# 06_-_PERIPHERAL.net
KiCad netlist of a schematic drawn in Altium Designer
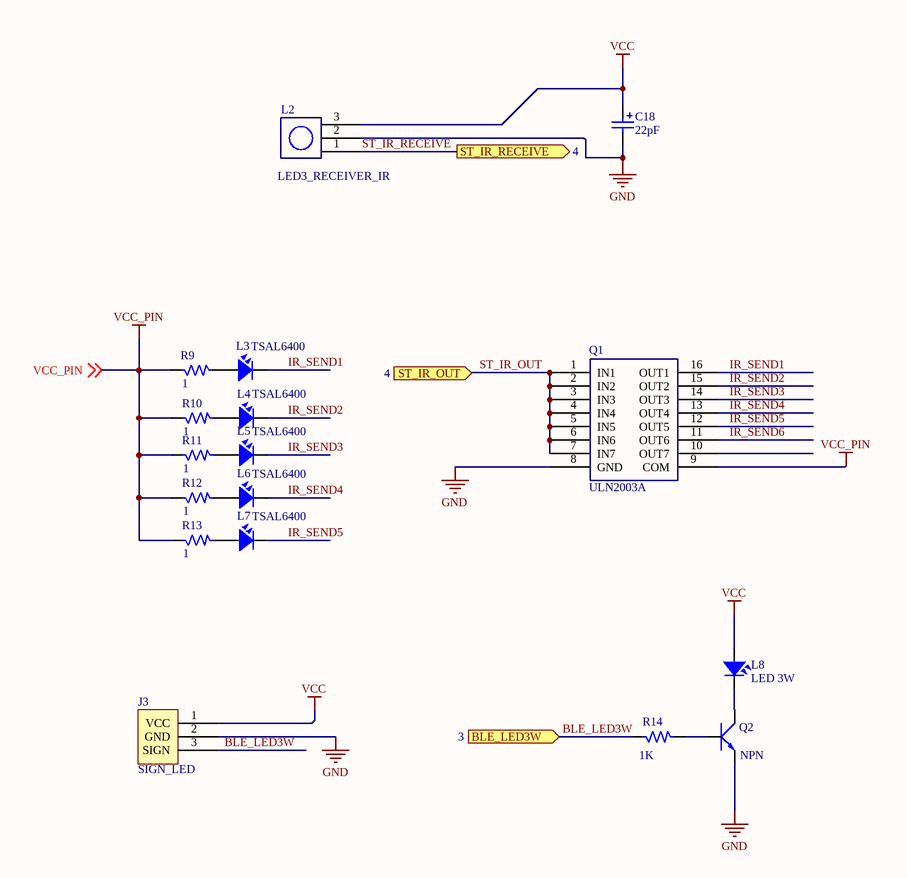
[diagram p0: [06] - PERIPHERAL.SchDoc]

(export (version "E")
  (design (tool "Eeschema 10.0.6"))
  (components
    (comp (ref "C18")
      (value "C_22pF_SMD0603_CERAMIC_50V")
      (footprint "CAP_SMD0603")
      (description "CAP CER 22PF 50V NP0 0603")
      (fields
        (field (name "MANUFACTURER") "Murata Electronics North America")
        (field (name "MANUFACTURER PART NUMBER") "GQM1885C1H220JB01D")
        (field (name "CAPACITANCE") "22pF")
      )
      (libsource (lib "ALTIUM_LIB") (part "C_22pF_SMD0603_CERAMIC_50V"))
    )
    (comp (ref "J3")
      (value "SIGN_LED")
      (footprint "HEADER3_SIGN_LED")
      (description "CONN HEADER VERT 3POS .100 TIN")
      (fields
        (field (name "MANUFACTURER") "TE Connectivity AMP Connectors")
        (field (name "MANUFACTURER PART NUMBER") "640456-3")
      )
      (libsource (lib "ALTIUM_LIB") (part "HEADER3_SIGN_LED_HOLE2.54"))
    )
    (comp (ref "L2")
      (value "LED3_RECEIVER_IR")
      (footprint "LED3_IR_RECEIVER")
      (description "RECEIVER IR REM CTRL 3V 38KHZ")
      (fields
        (field (name "MANUFACTURER") "Sharp Microelectronics")
        (field (name "MANUFACTURER PART NUMBER") "GP1UE261XKVF")
      )
      (libsource (lib "SchematicLib") (part "LED3_RECEIVER_IR_HOLE_38KHz_3V"))
    )
    (comp (ref "L3")
      (value "TSAL6400")
      (footprint "LED2_IR_TRANSMITOR")
      (description "EMITTER IR 940NM 100MA RADIAL")
      (fields (field (name "MANUFACTURER") "Vishay Semiconductor Opto Division"))
      (libsource (lib "ALTIUM_LIB") (part "LED2_TRANSMITER_IR_TSAL6400_HOLE_5MM"))
    )
    (comp (ref "L4")
      (value "TSAL6400")
      (footprint "LED2_IR_TRANSMITOR")
      (description "EMITTER IR 940NM 100MA RADIAL")
      (fields (field (name "MANUFACTURER") "Vishay Semiconductor Opto Division"))
      (libsource (lib "ALTIUM_LIB") (part "LED2_TRANSMITER_IR_TSAL6400_HOLE_5MM"))
    )
    (comp (ref "L5")
      (value "TSAL6400")
      (footprint "LED2_IR_TRANSMITOR")
      (description "EMITTER IR 940NM 100MA RADIAL")
      (fields (field (name "MANUFACTURER") "Vishay Semiconductor Opto Division"))
      (libsource (lib "ALTIUM_LIB") (part "LED2_TRANSMITER_IR_TSAL6400_HOLE_5MM"))
    )
    (comp (ref "L6")
      (value "TSAL6400")
      (footprint "LED2_IR_TRANSMITOR")
      (description "EMITTER IR 940NM 100MA RADIAL")
      (fields (field (name "MANUFACTURER") "Vishay Semiconductor Opto Division"))
      (libsource (lib "ALTIUM_LIB") (part "LED2_TRANSMITER_IR_TSAL6400_HOLE_5MM"))
    )
    (comp (ref "L7")
      (value "TSAL6400")
      (footprint "LED2_IR_TRANSMITOR")
      (description "EMITTER IR 940NM 100MA RADIAL")
      (fields (field (name "MANUFACTURER") "Vishay Semiconductor Opto Division"))
      (libsource (lib "ALTIUM_LIB") (part "LED2_TRANSMITER_IR_TSAL6400_HOLE_5MM"))
    )
    (comp (ref "L8")
      (value "LED 3W")
      (footprint "LED2_IR_TRANSMITOR")
      (description "EMITTER IR 940NM 100MA RADIAL")
      (fields
        (field (name "MANUFACTURER") "Vishay Semiconductor Opto Division")
        (field (name "MANUFACTURER PART NUMBER") "TSAL6400")
      )
      (libsource (lib "ALTIUM_LIB") (part "LED2_TRANSMITER_IR_TSAL6400_HOLE_5MM"))
    )
    (comp (ref "Q1")
      (value "ULN2003A")
      (footprint "TRAN7_ULN2003_16SOIC")
      (description "TRANS 7NPN DARL 50V 0.5A 16SO")
      (fields
        (field (name "MANUFACTURER") "Texas Instruments")
        (field (name "MANUFACTURER PART NUMBER") "ULN2003ADR")
      )
      (libsource (lib "ALTIUM_LIB") (part "TRAN_7NPN_SMD_16SOIC"))
    )
    (comp (ref "Q2")
      (value "NPN")
      (footprint "TRAN-NPN-SMD")
      (description "TRANS NPN 40V 0.2A SOT23")
      (fields
        (field (name "MANUFACTURER") "ON Semiconductor")
        (field (name "MANUFACTURER PART NUMBER") "MMBT3904LT1G")
      )
      (libsource (lib "ALTIUM_LIB") (part "TRAN_NPN_SMD_SOT23_0.2A_40V"))
    )
    (comp (ref "R9")
      (value "R_1OhM_SMD0603_1%_1/4W")
      (footprint "RES_SMD0603")
      (description "RES SMD 1 OHM 1% 1/4W 0603")
      (fields
        (field (name "MANUFACTURER") "Panasonic Electronic Components")
        (field (name "MANUFACTURER PART NUMBER") "ERJ-3BQF1R0V")
        (field (name "RESISTANCE (OHMS)") "1")
      )
      (libsource (lib "ALTIUM_LIB") (part "R_1OhM_SMD0603_1%_1/4W"))
    )
    (comp (ref "R10")
      (value "R_1OhM_SMD0603_1%_1/4W")
      (footprint "RES_SMD0603")
      (description "RES SMD 1 OHM 1% 1/4W 0603")
      (fields
        (field (name "MANUFACTURER") "Panasonic Electronic Components")
        (field (name "MANUFACTURER PART NUMBER") "ERJ-3BQF1R0V")
        (field (name "RESISTANCE (OHMS)") "1")
      )
      (libsource (lib "ALTIUM_LIB") (part "R_1OhM_SMD0603_1%_1/4W"))
    )
    (comp (ref "R11")
      (value "R_1OhM_SMD0603_1%_1/4W")
      (footprint "RES_SMD0603")
      (description "RES SMD 1 OHM 1% 1/4W 0603")
      (fields
        (field (name "MANUFACTURER") "Panasonic Electronic Components")
        (field (name "MANUFACTURER PART NUMBER") "ERJ-3BQF1R0V")
        (field (name "RESISTANCE (OHMS)") "1")
      )
      (libsource (lib "ALTIUM_LIB") (part "R_1OhM_SMD0603_1%_1/4W"))
    )
    (comp (ref "R12")
      (value "R_1OhM_SMD0603_1%_1/4W")
      (footprint "RES_SMD0603")
      (description "RES SMD 1 OHM 1% 1/4W 0603")
      (fields
        (field (name "MANUFACTURER") "Panasonic Electronic Components")
        (field (name "MANUFACTURER PART NUMBER") "ERJ-3BQF1R0V")
        (field (name "RESISTANCE (OHMS)") "1")
      )
      (libsource (lib "ALTIUM_LIB") (part "R_1OhM_SMD0603_1%_1/4W"))
    )
    (comp (ref "R13")
      (value "R_1OhM_SMD0603_1%_1/4W")
      (footprint "RES_SMD0603")
      (description "RES SMD 1 OHM 1% 1/4W 0603")
      (fields
        (field (name "MANUFACTURER") "Panasonic Electronic Components")
        (field (name "MANUFACTURER PART NUMBER") "ERJ-3BQF1R0V")
        (field (name "RESISTANCE (OHMS)") "1")
      )
      (libsource (lib "ALTIUM_LIB") (part "R_1OhM_SMD0603_1%_1/4W"))
    )
    (comp (ref "R14")
      (value "R_1K_SMD0603_1%_1/10W")
      (footprint "RES_SMD0603")
      (description "RES SMD 1K OHM 1% 1/10W 0603")
      (fields
        (field (name "MANUFACTURER") "Yageo")
        (field (name "MANUFACTURER PART NUMBER") "RC0603FR-071KL")
        (field (name "RESISTANCE (OHMS)") "1K")
      )
      (libsource (lib "ALTIUM_LIB") (part "R_1K_SMD0603_1%_1/10W"))
    )
  )
  (nets
    (net (code "1") (name "/BLE_LED3W") (class "Default")
      (node (ref "J3") (pin "3") (pinfunction "SIGN_3") (pintype "passive"))
      (node (ref "R14") (pin "1") (pinfunction "1_1") (pintype "passive"))
    )
    (net (code "2") (name "/IR_SEND1") (class "Default")
      (node (ref "L3") (pin "2") (pinfunction "2_2") (pintype "passive"))
      (node (ref "Q1") (pin "16") (pinfunction "OUT1_16") (pintype "passive"))
    )
    (net (code "3") (name "/IR_SEND2") (class "Default")
      (node (ref "L4") (pin "2") (pinfunction "2_2") (pintype "passive"))
      (node (ref "Q1") (pin "15") (pinfunction "OUT2_15") (pintype "passive"))
    )
    (net (code "4") (name "/IR_SEND3") (class "Default")
      (node (ref "L5") (pin "2") (pinfunction "2_2") (pintype "passive"))
      (node (ref "Q1") (pin "14") (pinfunction "OUT3_14") (pintype "passive"))
    )
    (net (code "5") (name "/IR_SEND4") (class "Default")
      (node (ref "L6") (pin "2") (pinfunction "2_2") (pintype "passive"))
      (node (ref "Q1") (pin "13") (pinfunction "OUT4_13") (pintype "passive"))
    )
    (net (code "6") (name "/IR_SEND5") (class "Default")
      (node (ref "L7") (pin "2") (pinfunction "2_2") (pintype "passive"))
      (node (ref "Q1") (pin "12") (pinfunction "OUT5_12") (pintype "passive"))
    )
    (net (code "7") (name "/IR_SEND6") (class "Default")
      (node (ref "Q1") (pin "11") (pinfunction "OUT6_11") (pintype "passive"))
    )
    (net (code "8") (name "/ST_IR_OUT") (class "Default")
      (node (ref "Q1") (pin "1") (pinfunction "IN1_1") (pintype "passive"))
      (node (ref "Q1") (pin "2") (pinfunction "IN2_2") (pintype "passive"))
      (node (ref "Q1") (pin "3") (pinfunction "IN3_3") (pintype "passive"))
      (node (ref "Q1") (pin "4") (pinfunction "IN4_4") (pintype "passive"))
      (node (ref "Q1") (pin "5") (pinfunction "IN5_5") (pintype "passive"))
      (node (ref "Q1") (pin "6") (pinfunction "IN6_6") (pintype "passive"))
      (node (ref "Q1") (pin "7") (pinfunction "IN7_7") (pintype "passive"))
    )
    (net (code "9") (name "/ST_IR_RECEIVE") (class "Default")
      (node (ref "L2") (pin "1") (pinfunction "OUT_1") (pintype "passive"))
    )
    (net (code "10") (name "GND") (class "Default")
      (node (ref "C18") (pin "2") (pinfunction "2_2") (pintype "passive"))
      (node (ref "J3") (pin "2") (pinfunction "GND_2") (pintype "passive"))
      (node (ref "L2") (pin "2") (pinfunction "GND_2") (pintype "passive"))
      (node (ref "Q1") (pin "8") (pinfunction "GND_8") (pintype "passive"))
      (node (ref "Q2") (pin "2") (pinfunction "E_2") (pintype "passive"))
    )
    (net (code "11") (name "Net-(L3-Pad1)") (class "Default")
      (node (ref "L3") (pin "1") (pinfunction "1_1") (pintype "passive"))
      (node (ref "R9") (pin "2") (pinfunction "2_2") (pintype "passive"))
    )
    (net (code "12") (name "Net-(L4-Pad1)") (class "Default")
      (node (ref "L4") (pin "1") (pinfunction "1_1") (pintype "passive"))
      (node (ref "R10") (pin "2") (pinfunction "2_2") (pintype "passive"))
    )
    (net (code "13") (name "Net-(L5-Pad1)") (class "Default")
      (node (ref "L5") (pin "1") (pinfunction "1_1") (pintype "passive"))
      (node (ref "R11") (pin "2") (pinfunction "2_2") (pintype "passive"))
    )
    (net (code "14") (name "Net-(L6-Pad1)") (class "Default")
      (node (ref "L6") (pin "1") (pinfunction "1_1") (pintype "passive"))
      (node (ref "R12") (pin "2") (pinfunction "2_2") (pintype "passive"))
    )
    (net (code "15") (name "Net-(L7-Pad1)") (class "Default")
      (node (ref "L7") (pin "1") (pinfunction "1_1") (pintype "passive"))
      (node (ref "R13") (pin "2") (pinfunction "2_2") (pintype "passive"))
    )
    (net (code "16") (name "Net-(Q2-B)") (class "Default")
      (node (ref "Q2") (pin "1") (pinfunction "B_1") (pintype "passive"))
      (node (ref "R14") (pin "2") (pinfunction "2_2") (pintype "passive"))
    )
    (net (code "17") (name "Net-(Q2-C)") (class "Default")
      (node (ref "L8") (pin "2") (pinfunction "2_2") (pintype "passive"))
      (node (ref "Q2") (pin "3") (pinfunction "C_3") (pintype "passive"))
    )
    (net (code "18") (name "VCC") (class "Default")
      (node (ref "C18") (pin "1") (pinfunction "1_1") (pintype "passive"))
      (node (ref "J3") (pin "1") (pinfunction "VCC_1") (pintype "passive"))
      (node (ref "L2") (pin "3") (pinfunction "VCC_3") (pintype "passive"))
      (node (ref "L8") (pin "1") (pinfunction "1_1") (pintype "passive"))
    )
    (net (code "19") (name "VCC_PIN") (class "Default")
      (node (ref "Q1") (pin "9") (pinfunction "COM_9") (pintype "passive"))
      (node (ref "R10") (pin "1") (pinfunction "1_1") (pintype "passive"))
      (node (ref "R11") (pin "1") (pinfunction "1_1") (pintype "passive"))
      (node (ref "R12") (pin "1") (pinfunction "1_1") (pintype "passive"))
      (node (ref "R13") (pin "1") (pinfunction "1_1") (pintype "passive"))
      (node (ref "R9") (pin "1") (pinfunction "1_1") (pintype "passive"))
    )
    (net (code "20") (name "unconnected-(Q1-OUT7-Pad10)") (class "Default")
      (node (ref "Q1") (pin "10") (pinfunction "OUT7_10") (pintype "passive"))
    )
  )
)
